# Spring2020V1_4.net
KiCad netlist of a schematic drawn in EAGLE
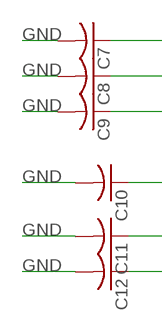
[diagram p0: schematic, sheet 1, part 1 of 2]
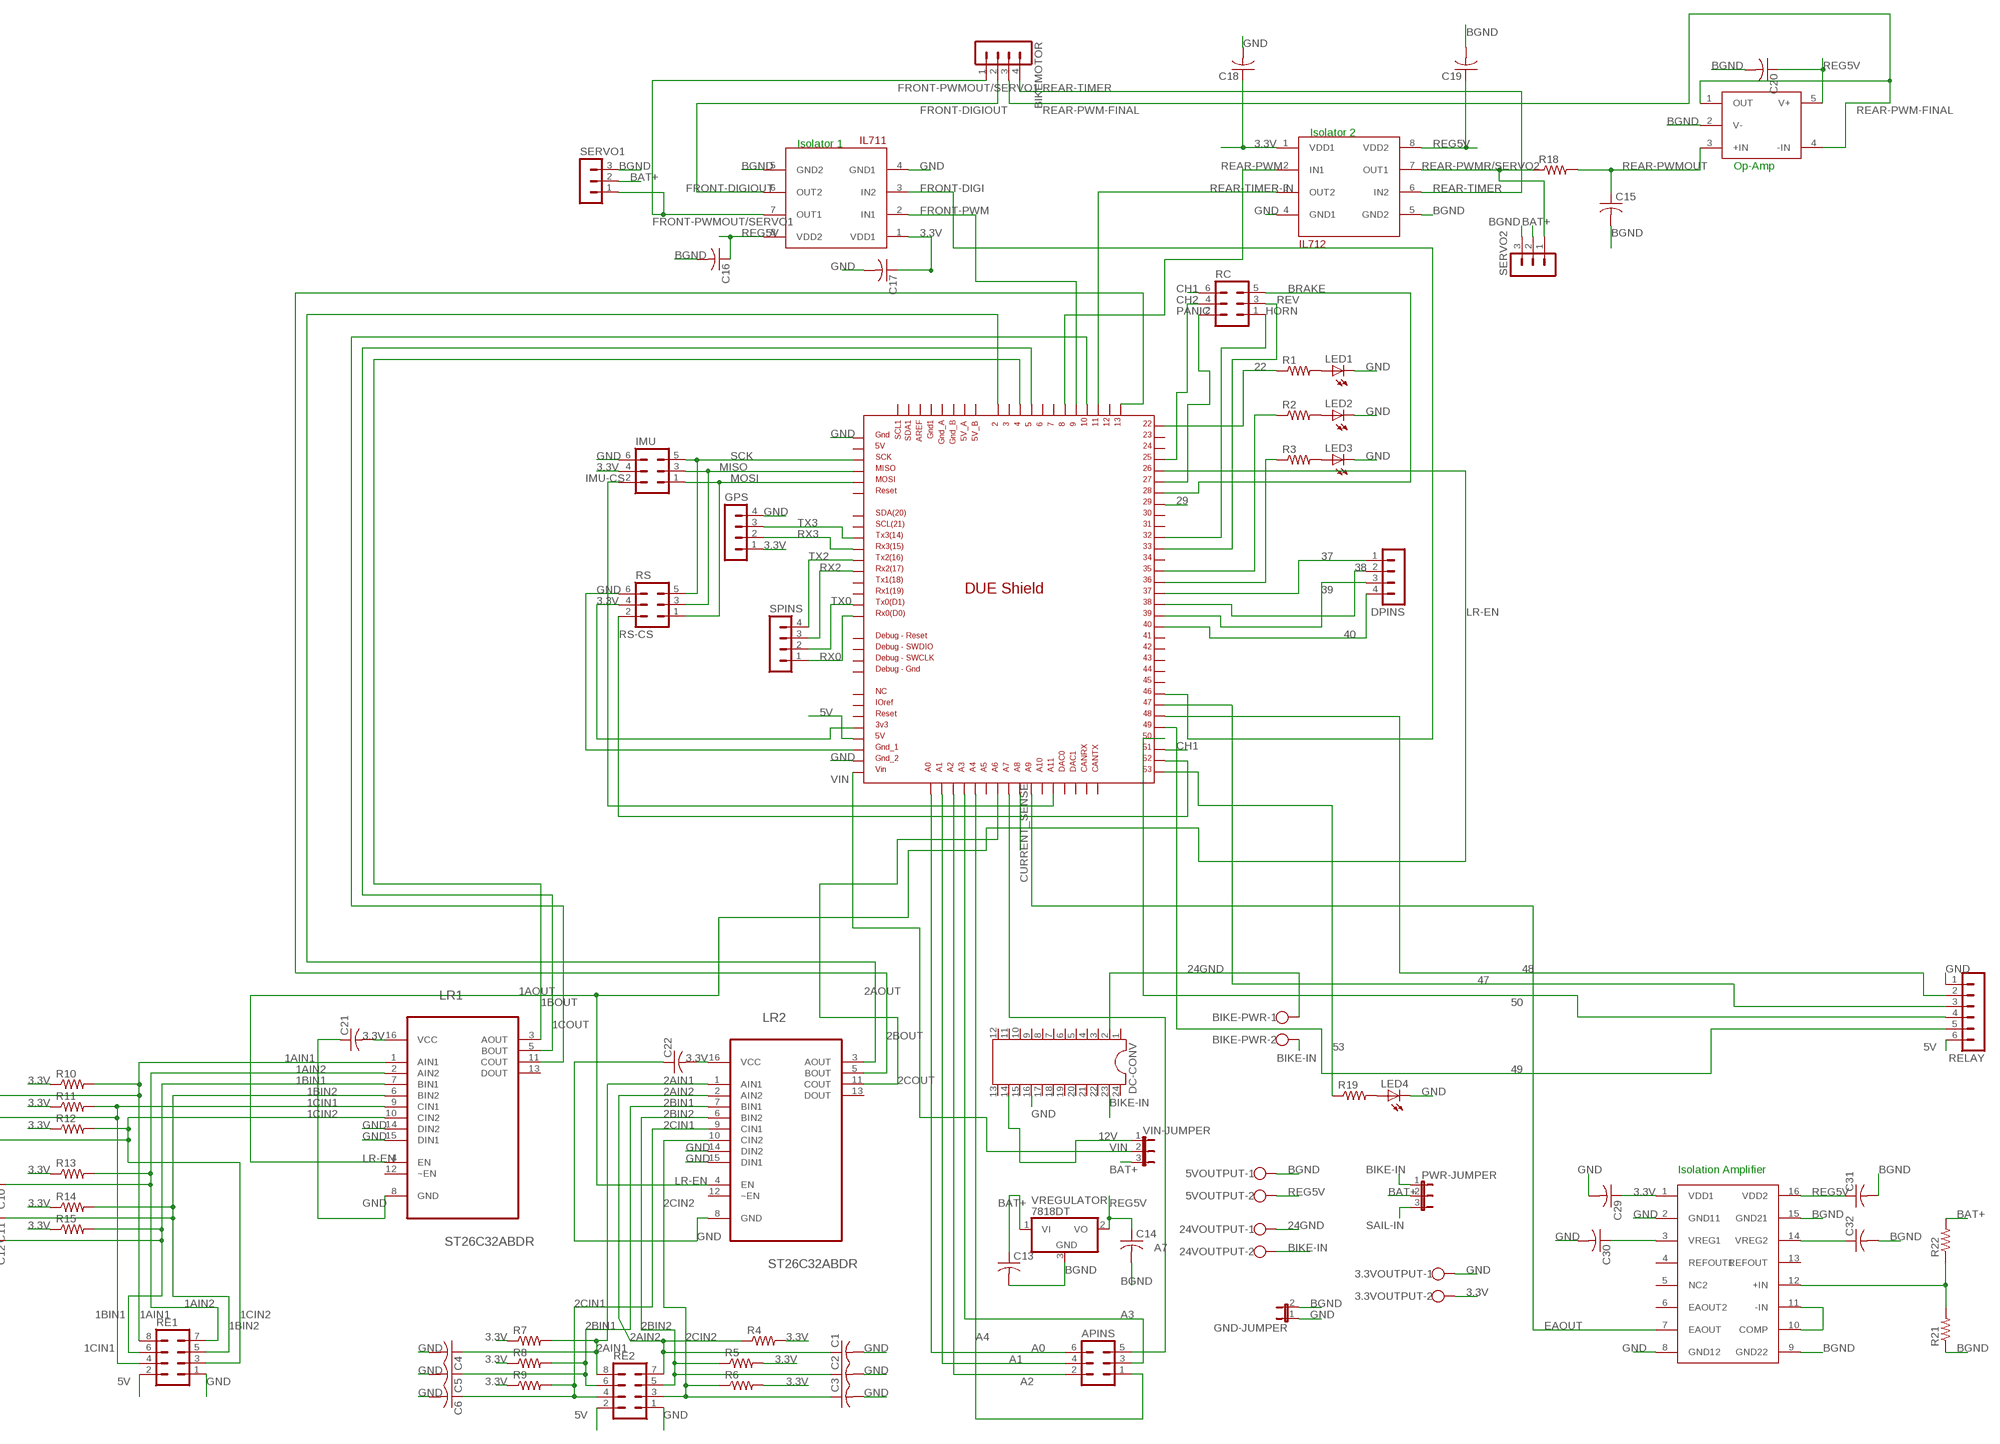
[diagram p1: schematic, sheet 1, part 2 of 2]

(export (version "E")
  (design (tool "Eeschema 10.0.6"))
  (components
    (comp (ref "3.3VOUTPUT")
      (value "W237-102")
      (footprint "eagle-import:W237-102")
      (fields (field (name "MPN") "237-102"))
      (libsource (lib "eagle-import") (part "W237-102"))
    )
    (comp (ref "5VOUTPUT")
      (value "W237-102")
      (footprint "eagle-import:W237-102")
      (fields (field (name "MPN") "237-102"))
      (libsource (lib "eagle-import") (part "W237-102"))
    )
    (comp (ref "24VOUTPUT")
      (value "W237-102")
      (footprint "eagle-import:W237-102")
      (fields (field (name "MPN") "237-102"))
      (libsource (lib "eagle-import") (part "W237-102"))
    )
    (comp (ref "APINS")
      (value "MA03-2")
      (footprint "eagle-import:MA03-2")
      (libsource (lib "eagle-import") (part "MA03-2"))
    )
    (comp (ref "BIKE-PWR")
      (value "W237-102")
      (footprint "eagle-import:W237-102")
      (fields (field (name "MPN") "237-102"))
      (libsource (lib "eagle-import") (part "W237-102"))
    )
    (comp (ref "BIKEMOTOR")
      (value "MA04-1")
      (footprint "eagle-import:MA04-1")
      (libsource (lib "eagle-import") (part "MA04-1"))
    )
    (comp (ref "C1")
      (value "C-US025-025X050")
      (footprint "eagle-import:C025-025X050")
      (libsource (lib "eagle-import") (part "C-US025-025X050"))
    )
    (comp (ref "C2")
      (value "C-US025-025X050")
      (footprint "eagle-import:C025-025X050")
      (libsource (lib "eagle-import") (part "C-US025-025X050"))
    )
    (comp (ref "C3")
      (value "C-US025-025X050")
      (footprint "eagle-import:C025-025X050")
      (libsource (lib "eagle-import") (part "C-US025-025X050"))
    )
    (comp (ref "C4")
      (value "C-US025-025X050")
      (footprint "eagle-import:C025-025X050")
      (libsource (lib "eagle-import") (part "C-US025-025X050"))
    )
    (comp (ref "C5")
      (value "C-US025-025X050")
      (footprint "eagle-import:C025-025X050")
      (libsource (lib "eagle-import") (part "C-US025-025X050"))
    )
    (comp (ref "C6")
      (value "C-US025-025X050")
      (footprint "eagle-import:C025-025X050")
      (libsource (lib "eagle-import") (part "C-US025-025X050"))
    )
    (comp (ref "C7")
      (value "C-US025-025X050")
      (footprint "eagle-import:C025-025X050")
      (libsource (lib "eagle-import") (part "C-US025-025X050"))
    )
    (comp (ref "C8")
      (value "C-US025-025X050")
      (footprint "eagle-import:C025-025X050")
      (libsource (lib "eagle-import") (part "C-US025-025X050"))
    )
    (comp (ref "C9")
      (value "C-US025-025X050")
      (footprint "eagle-import:C025-025X050")
      (libsource (lib "eagle-import") (part "C-US025-025X050"))
    )
    (comp (ref "C10")
      (value "C-US025-025X050")
      (footprint "eagle-import:C025-025X050")
      (libsource (lib "eagle-import") (part "C-US025-025X050"))
    )
    (comp (ref "C11")
      (value "C-US025-025X050")
      (footprint "eagle-import:C025-025X050")
      (libsource (lib "eagle-import") (part "C-US025-025X050"))
    )
    (comp (ref "C12")
      (value "C-US025-025X050")
      (footprint "eagle-import:C025-025X050")
      (libsource (lib "eagle-import") (part "C-US025-025X050"))
    )
    (comp (ref "C13")
      (value "C-US025-050X050")
      (footprint "eagle-import:C025-050X050")
      (libsource (lib "eagle-import") (part "C-US025-050X050"))
    )
    (comp (ref "C14")
      (value "C-US025-050X050")
      (footprint "eagle-import:C025-050X050")
      (libsource (lib "eagle-import") (part "C-US025-050X050"))
    )
    (comp (ref "C15")
      (value "C-US025-050X050")
      (footprint "eagle-import:C025-050X050")
      (libsource (lib "eagle-import") (part "C-US025-050X050"))
    )
    (comp (ref "C16")
      (value "C-US025-050X050")
      (footprint "eagle-import:C025-050X050")
      (libsource (lib "eagle-import") (part "C-US025-050X050"))
    )
    (comp (ref "C17")
      (value "C-US025-050X050")
      (footprint "eagle-import:C025-050X050")
      (libsource (lib "eagle-import") (part "C-US025-050X050"))
    )
    (comp (ref "C18")
      (value "C-US025-050X050")
      (footprint "eagle-import:C025-050X050")
      (libsource (lib "eagle-import") (part "C-US025-050X050"))
    )
    (comp (ref "C19")
      (value "C-US025-050X050")
      (footprint "eagle-import:C025-050X050")
      (libsource (lib "eagle-import") (part "C-US025-050X050"))
    )
    (comp (ref "C20")
      (value "C-US025-050X050")
      (footprint "eagle-import:C025-050X050")
      (libsource (lib "eagle-import") (part "C-US025-050X050"))
    )
    (comp (ref "C21")
      (value "C-US025-050X050")
      (footprint "eagle-import:C025-050X050")
      (libsource (lib "eagle-import") (part "C-US025-050X050"))
    )
    (comp (ref "C22")
      (value "C-US025-050X050")
      (footprint "eagle-import:C025-050X050")
      (libsource (lib "eagle-import") (part "C-US025-050X050"))
    )
    (comp (ref "C29")
      (value "C-US025-050X050")
      (footprint "eagle-import:C025-050X050")
      (libsource (lib "eagle-import") (part "C-US025-050X050"))
    )
    (comp (ref "C30")
      (value "C-US025-050X050")
      (footprint "eagle-import:C025-050X050")
      (libsource (lib "eagle-import") (part "C-US025-050X050"))
    )
    (comp (ref "C31")
      (value "C-US025-050X050")
      (footprint "eagle-import:C025-050X050")
      (libsource (lib "eagle-import") (part "C-US025-050X050"))
    )
    (comp (ref "C32")
      (value "C-US025-050X050")
      (footprint "eagle-import:C025-050X050")
      (libsource (lib "eagle-import") (part "C-US025-050X050"))
    )
    (comp (ref "DC-CONV")
      (value "CU.INC---VAWQ6-Q48-S12H-6")
      (footprint "eagle-import:DIL24-6")
      (libsource (lib "eagle-import") (part "CU.INC---VAWQ6-Q48-S12H-6"))
    )
    (comp (ref "DPINS")
      (value "MA04-1")
      (footprint "eagle-import:MA04-1")
      (libsource (lib "eagle-import") (part "MA04-1"))
    )
    (comp (ref "GND-JUMPER")
      (value "JP1E")
      (footprint "eagle-import:JP1")
      (libsource (lib "eagle-import") (part "JP1E"))
    )
    (comp (ref "GPS")
      (value "MA04-1")
      (footprint "eagle-import:MA04-1")
      (libsource (lib "eagle-import") (part "MA04-1"))
    )
    (comp (ref "IMU")
      (value "MA03-2")
      (footprint "eagle-import:MA03-2")
      (libsource (lib "eagle-import") (part "MA03-2"))
    )
    (comp (ref "LED1")
      (value "LED5MM")
      (footprint "eagle-import:LED5MM")
      (libsource (lib "eagle-import") (part "LED5MM"))
    )
    (comp (ref "LED2")
      (value "LED5MM")
      (footprint "eagle-import:LED5MM")
      (libsource (lib "eagle-import") (part "LED5MM"))
    )
    (comp (ref "LED3")
      (value "LED5MM")
      (footprint "eagle-import:LED5MM")
      (libsource (lib "eagle-import") (part "LED5MM"))
    )
    (comp (ref "LED4")
      (value "LED5MM")
      (footprint "eagle-import:LED5MM")
      (libsource (lib "eagle-import") (part "LED5MM"))
    )
    (comp (ref "LR1")
      (value "ST26C32ABDR")
      (footprint "eagle-import:SOIC127P600X175-16N")
      (libsource (lib "eagle-import") (part "ST26C32ABDR"))
    )
    (comp (ref "LR2")
      (value "ST26C32ABDR")
      (footprint "eagle-import:SOIC127P600X175-16N")
      (libsource (lib "eagle-import") (part "ST26C32ABDR"))
    )
    (comp (ref "OP-AMP")
      (value "OPAMP")
      (footprint "eagle-import:SOT95P280X145-5N")
      (libsource (lib "eagle-import") (part "OPAMP"))
    )
    (comp (ref "PWR-JUMPER")
      (value "JP2E")
      (footprint "eagle-import:JP2")
      (libsource (lib "eagle-import") (part "JP2E"))
    )
    (comp (ref "R1")
      (value "R-US_0309/10")
      (footprint "eagle-import:0309_10")
      (libsource (lib "eagle-import") (part "R-US_0309/10"))
    )
    (comp (ref "R2")
      (value "R-US_0309/10")
      (footprint "eagle-import:0309_10")
      (libsource (lib "eagle-import") (part "R-US_0309/10"))
    )
    (comp (ref "R3")
      (value "R-US_0309/10")
      (footprint "eagle-import:0309_10")
      (libsource (lib "eagle-import") (part "R-US_0309/10"))
    )
    (comp (ref "R4")
      (value "R-US_0613/15")
      (footprint "eagle-import:P0613_15")
      (libsource (lib "eagle-import") (part "resistor_R-US_0613/15"))
    )
    (comp (ref "R5")
      (value "R-US_0613/15")
      (footprint "eagle-import:P0613_15")
      (libsource (lib "eagle-import") (part "resistor_R-US_0613/15"))
    )
    (comp (ref "R6")
      (value "R-US_0613/15")
      (footprint "eagle-import:P0613_15")
      (libsource (lib "eagle-import") (part "resistor_R-US_0613/15"))
    )
    (comp (ref "R7")
      (value "R-US_0613/15")
      (footprint "eagle-import:P0613_15")
      (libsource (lib "eagle-import") (part "resistor_R-US_0613/15"))
    )
    (comp (ref "R8")
      (value "R-US_0613/15")
      (footprint "eagle-import:P0613_15")
      (libsource (lib "eagle-import") (part "resistor_R-US_0613/15"))
    )
    (comp (ref "R9")
      (value "R-US_0613/15")
      (footprint "eagle-import:P0613_15")
      (libsource (lib "eagle-import") (part "resistor_R-US_0613/15"))
    )
    (comp (ref "R10")
      (value "R-US_0613/15")
      (footprint "eagle-import:P0613_15")
      (libsource (lib "eagle-import") (part "resistor_R-US_0613/15"))
    )
    (comp (ref "R11")
      (value "R-US_0613/15")
      (footprint "eagle-import:P0613_15")
      (libsource (lib "eagle-import") (part "resistor_R-US_0613/15"))
    )
    (comp (ref "R12")
      (value "R-US_0613/15")
      (footprint "eagle-import:P0613_15")
      (libsource (lib "eagle-import") (part "resistor_R-US_0613/15"))
    )
    (comp (ref "R13")
      (value "R-US_0613/15")
      (footprint "eagle-import:P0613_15")
      (libsource (lib "eagle-import") (part "resistor_R-US_0613/15"))
    )
    (comp (ref "R14")
      (value "R-US_0613/15")
      (footprint "eagle-import:P0613_15")
      (libsource (lib "eagle-import") (part "resistor_R-US_0613/15"))
    )
    (comp (ref "R15")
      (value "R-US_0613/15")
      (footprint "eagle-import:P0613_15")
      (libsource (lib "eagle-import") (part "resistor_R-US_0613/15"))
    )
    (comp (ref "R18")
      (value "R-US_0414/15")
      (footprint "eagle-import:0414_15")
      (libsource (lib "eagle-import") (part "resistor_R-US_0414/15"))
    )
    (comp (ref "R19")
      (value "R-US_0309/10")
      (footprint "eagle-import:0309_10")
      (libsource (lib "eagle-import") (part "R-US_0309/10"))
    )
    (comp (ref "R21")
      (value "R-US_0414/15")
      (footprint "eagle-import:0414_15")
      (libsource (lib "eagle-import") (part "resistor_R-US_0414/15"))
    )
    (comp (ref "R22")
      (value "R-US_0414/15")
      (footprint "eagle-import:0414_15")
      (libsource (lib "eagle-import") (part "resistor_R-US_0414/15"))
    )
    (comp (ref "RC")
      (value "MA03-2")
      (footprint "eagle-import:MA03-2")
      (libsource (lib "eagle-import") (part "MA03-2"))
    )
    (comp (ref "RE1")
      (value "MA04-2")
      (footprint "eagle-import:MA04-2")
      (libsource (lib "eagle-import") (part "MA04-2"))
    )
    (comp (ref "RE2")
      (value "MA04-2")
      (footprint "eagle-import:MA04-2")
      (libsource (lib "eagle-import") (part "MA04-2"))
    )
    (comp (ref "RELAY")
      (value "MA06-1")
      (footprint "eagle-import:MA06-1")
      (libsource (lib "eagle-import") (part "MA06-1"))
    )
    (comp (ref "RS")
      (value "MA03-2")
      (footprint "eagle-import:MA03-2")
      (libsource (lib "eagle-import") (part "MA03-2"))
    )
    (comp (ref "SERVO1")
      (value "MA03-1")
      (footprint "eagle-import:MA03-1")
      (libsource (lib "eagle-import") (part "MA03-1"))
    )
    (comp (ref "SERVO2")
      (value "MA03-1")
      (footprint "eagle-import:MA03-1")
      (libsource (lib "eagle-import") (part "MA03-1"))
    )
    (comp (ref "SPINS")
      (value "MA04-1")
      (footprint "eagle-import:MA04-1")
      (libsource (lib "eagle-import") (part "MA04-1"))
    )
    (comp (ref "U$1")
      (value "DUE(NORMAL)")
      (footprint "eagle-import:DUE(NORMAL)")
      (libsource (lib "eagle-import") (part "DUE(NORMAL)"))
    )
    (comp (ref "U$2")
      (value "IL-711")
      (footprint "eagle-import:8PINSOIC")
      (libsource (lib "eagle-import") (part "IL-711"))
    )
    (comp (ref "U$5")
      (value "ISOLATED_ERROR_AMP_ADUM3190")
      (footprint "eagle-import:QSOP16")
      (libsource (lib "eagle-import") (part "ISOLATED_ERROR_AMP_ADUM3190"))
    )
    (comp (ref "U$7")
      (value "IL-712")
      (footprint "eagle-import:8PINSOIC")
      (libsource (lib "eagle-import") (part "IL-712"))
    )
    (comp (ref "VIN-JUMPER")
      (value "JP2E")
      (footprint "eagle-import:JP2")
      (libsource (lib "eagle-import") (part "JP2E"))
    )
    (comp (ref "VREGULATOR")
      (value "7818DT")
      (footprint "eagle-import:TO252")
      (libsource (lib "eagle-import") (part "78DT18"))
    )
  )
  (nets
    (net (code "1") (name "/1AIN1") (class "Default")
      (node (ref "C7") (pin "1") (pinfunction "1_1") (pintype "passive"))
      (node (ref "LR1") (pin "1") (pinfunction "AIN1_1") (pintype "input"))
      (node (ref "R10") (pin "2") (pinfunction "2_2") (pintype "passive"))
      (node (ref "RE1") (pin "8") (pinfunction "8_8") (pintype "passive"))
    )
    (net (code "2") (name "/1AIN2") (class "Default")
      (node (ref "C10") (pin "1") (pinfunction "1_1") (pintype "passive"))
      (node (ref "LR1") (pin "2") (pinfunction "AIN2_2") (pintype "input"))
      (node (ref "R13") (pin "2") (pinfunction "2_2") (pintype "passive"))
      (node (ref "RE1") (pin "7") (pinfunction "7_7") (pintype "passive"))
    )
    (net (code "3") (name "/1AOUT") (class "Default")
      (node (ref "LR1") (pin "3") (pinfunction "AOUT_3") (pintype "output"))
      (node (ref "U$1") (pin "4") (pinfunction "4_4") (pintype "bidirectional"))
    )
    (net (code "4") (name "/1BIN1") (class "Default")
      (node (ref "C12") (pin "1") (pinfunction "1_1") (pintype "passive"))
      (node (ref "LR1") (pin "7") (pinfunction "BIN1_7") (pintype "input"))
      (node (ref "R15") (pin "2") (pinfunction "2_2") (pintype "passive"))
      (node (ref "RE1") (pin "6") (pinfunction "6_6") (pintype "passive"))
    )
    (net (code "5") (name "/1BIN2") (class "Default")
      (node (ref "C11") (pin "1") (pinfunction "1_1") (pintype "passive"))
      (node (ref "LR1") (pin "6") (pinfunction "BIN2_6") (pintype "input"))
      (node (ref "R14") (pin "2") (pinfunction "2_2") (pintype "passive"))
      (node (ref "RE1") (pin "5") (pinfunction "5_5") (pintype "passive"))
    )
    (net (code "6") (name "/1BOUT") (class "Default")
      (node (ref "LR1") (pin "5") (pinfunction "BOUT_5") (pintype "output"))
      (node (ref "U$1") (pin "5") (pinfunction "5_5") (pintype "bidirectional"))
    )
    (net (code "7") (name "/1CIN1") (class "Default")
      (node (ref "C8") (pin "1") (pinfunction "1_1") (pintype "passive"))
      (node (ref "LR1") (pin "9") (pinfunction "CIN1_9") (pintype "input"))
      (node (ref "R11") (pin "2") (pinfunction "2_2") (pintype "passive"))
      (node (ref "RE1") (pin "4") (pinfunction "4_4") (pintype "passive"))
    )
    (net (code "8") (name "/1CIN2") (class "Default")
      (node (ref "C9") (pin "1") (pinfunction "1_1") (pintype "passive"))
      (node (ref "LR1") (pin "10") (pinfunction "CIN2_10") (pintype "input"))
      (node (ref "R12") (pin "2") (pinfunction "2_2") (pintype "passive"))
      (node (ref "RE1") (pin "3") (pinfunction "3_3") (pintype "passive"))
    )
    (net (code "9") (name "/1COUT") (class "Default")
      (node (ref "LR1") (pin "11") (pinfunction "COUT_11") (pintype "output"))
      (node (ref "U$1") (pin "10") (pinfunction "10_10") (pintype "bidirectional"))
    )
    (net (code "10") (name "/2AIN1") (class "Default")
      (node (ref "C4") (pin "1") (pinfunction "1_1") (pintype "passive"))
      (node (ref "LR2") (pin "1") (pinfunction "AIN1_1") (pintype "input"))
      (node (ref "R7") (pin "2") (pinfunction "2_2") (pintype "passive"))
      (node (ref "RE2") (pin "8") (pinfunction "8_8") (pintype "passive"))
    )
    (net (code "11") (name "/2AIN2") (class "Default")
      (node (ref "C1") (pin "1") (pinfunction "1_1") (pintype "passive"))
      (node (ref "LR2") (pin "2") (pinfunction "AIN2_2") (pintype "input"))
      (node (ref "R4") (pin "1") (pinfunction "1_1") (pintype "passive"))
      (node (ref "RE2") (pin "7") (pinfunction "7_7") (pintype "passive"))
    )
    (net (code "12") (name "/2AOUT") (class "Default")
      (node (ref "LR2") (pin "3") (pinfunction "AOUT_3") (pintype "output"))
      (node (ref "U$1") (pin "2") (pinfunction "2_2") (pintype "bidirectional"))
    )
    (net (code "13") (name "/2BIN1") (class "Default")
      (node (ref "C5") (pin "1") (pinfunction "1_1") (pintype "passive"))
      (node (ref "LR2") (pin "7") (pinfunction "BIN1_7") (pintype "input"))
      (node (ref "R8") (pin "2") (pinfunction "2_2") (pintype "passive"))
      (node (ref "RE2") (pin "6") (pinfunction "6_6") (pintype "passive"))
    )
    (net (code "14") (name "/2BIN2") (class "Default")
      (node (ref "C2") (pin "1") (pinfunction "1_1") (pintype "passive"))
      (node (ref "LR2") (pin "6") (pinfunction "BIN2_6") (pintype "input"))
      (node (ref "R5") (pin "1") (pinfunction "1_1") (pintype "passive"))
      (node (ref "RE2") (pin "5") (pinfunction "5_5") (pintype "passive"))
    )
    (net (code "15") (name "/2BOUT") (class "Default")
      (node (ref "LR2") (pin "5") (pinfunction "BOUT_5") (pintype "output"))
      (node (ref "U$1") (pin "13") (pinfunction "13_13") (pintype "bidirectional"))
    )
    (net (code "16") (name "/2CIN1") (class "Default")
      (node (ref "C6") (pin "1") (pinfunction "1_1") (pintype "passive"))
      (node (ref "LR2") (pin "9") (pinfunction "CIN1_9") (pintype "input"))
      (node (ref "R9") (pin "2") (pinfunction "2_2") (pintype "passive"))
      (node (ref "RE2") (pin "4") (pinfunction "4_4") (pintype "passive"))
    )
    (net (code "17") (name "/2CIN2") (class "Default")
      (node (ref "C3") (pin "1") (pinfunction "1_1") (pintype "passive"))
      (node (ref "LR2") (pin "10") (pinfunction "CIN2_10") (pintype "input"))
      (node (ref "R6") (pin "1") (pinfunction "1_1") (pintype "passive"))
      (node (ref "RE2") (pin "3") (pinfunction "3_3") (pintype "passive"))
    )
    (net (code "18") (name "/2COUT") (class "Default")
      (node (ref "LR2") (pin "11") (pinfunction "COUT_11") (pintype "output"))
      (node (ref "U$1") (pin "A6") (pinfunction "A6_A6") (pintype "bidirectional"))
    )
    (net (code "19") (name "/3.3V") (class "Default")
      (node (ref "3.3VOUTPUT") (pin "2") (pinfunction "KL_2") (pintype "passive"))
      (node (ref "C17") (pin "1") (pinfunction "1_1") (pintype "passive"))
      (node (ref "C18") (pin "1") (pinfunction "1_1") (pintype "passive"))
      (node (ref "C21") (pin "2") (pinfunction "2_2") (pintype "passive"))
      (node (ref "C22") (pin "2") (pinfunction "2_2") (pintype "passive"))
      (node (ref "C29") (pin "1") (pinfunction "1_1") (pintype "passive"))
      (node (ref "GPS") (pin "1") (pinfunction "1_1") (pintype "passive"))
      (node (ref "IMU") (pin "4") (pinfunction "4_4") (pintype "passive"))
      (node (ref "LR1") (pin "16") (pinfunction "VCC_16") (pintype "power_in"))
      (node (ref "LR2") (pin "16") (pinfunction "VCC_16") (pintype "power_in"))
      (node (ref "R10") (pin "1") (pinfunction "1_1") (pintype "passive"))
      (node (ref "R11") (pin "1") (pinfunction "1_1") (pintype "passive"))
      (node (ref "R12") (pin "1") (pinfunction "1_1") (pintype "passive"))
      (node (ref "R13") (pin "1") (pinfunction "1_1") (pintype "passive"))
      (node (ref "R14") (pin "1") (pinfunction "1_1") (pintype "passive"))
      (node (ref "R15") (pin "1") (pinfunction "1_1") (pintype "passive"))
      (node (ref "R4") (pin "2") (pinfunction "2_2") (pintype "passive"))
      (node (ref "R5") (pin "2") (pinfunction "2_2") (pintype "passive"))
      (node (ref "R6") (pin "2") (pinfunction "2_2") (pintype "passive"))
      (node (ref "R7") (pin "1") (pinfunction "1_1") (pintype "passive"))
      (node (ref "R8") (pin "1") (pinfunction "1_1") (pintype "passive"))
      (node (ref "R9") (pin "1") (pinfunction "1_1") (pintype "passive"))
      (node (ref "RS") (pin "4") (pinfunction "4_4") (pintype "passive"))
      (node (ref "U$1") (pin "3V3") (pinfunction "3V3_3V3") (pintype "bidirectional"))
      (node (ref "U$2") (pin "1") (pinfunction "VDD1_1") (pintype "power_in"))
      (node (ref "U$5") (pin "1") (pinfunction "VDD1_1") (pintype "bidirectional"))
      (node (ref "U$7") (pin "1") (pinfunction "VDD1_1") (pintype "power_in"))
    )
    (net (code "20") (name "/5V") (class "Default")
      (node (ref "RE1") (pin "2") (pinfunction "2_2") (pintype "passive"))
      (node (ref "RE2") (pin "2") (pinfunction "2_2") (pintype "passive"))
      (node (ref "RELAY") (pin "6") (pinfunction "6_6") (pintype "passive"))
      (node (ref "U$1") (pin "5V") (pinfunction "5V_5V") (pintype "bidirectional"))
    )
    (net (code "21") (name "/12V") (class "Default")
      (node (ref "DC-CONV") (pin "14") (pinfunction "14_14") (pintype "passive"))
      (node (ref "VIN-JUMPER") (pin "1") (pinfunction "1_1") (pintype "passive"))
    )
    (net (code "22") (name "/22") (class "Default")
      (node (ref "R1") (pin "1") (pinfunction "1_1") (pintype "passive"))
      (node (ref "U$1") (pin "22") (pinfunction "22_22") (pintype "bidirectional"))
    )
    (net (code "23") (name "/24GND") (class "Default")
      (node (ref "24VOUTPUT") (pin "1") (pinfunction "KL_1") (pintype "passive"))
      (node (ref "BIKE-PWR") (pin "1") (pinfunction "KL_1") (pintype "passive"))
      (node (ref "DC-CONV") (pin "2") (pinfunction "2_2") (pintype "passive"))
    )
    (net (code "24") (name "/29") (class "Default")
      (node (ref "U$1") (pin "29") (pinfunction "29_29") (pintype "bidirectional"))
    )
    (net (code "25") (name "/37") (class "Default")
      (node (ref "DPINS") (pin "1") (pinfunction "1_1") (pintype "passive"))
      (node (ref "U$1") (pin "37") (pinfunction "37_37") (pintype "bidirectional"))
    )
    (net (code "26") (name "/38") (class "Default")
      (node (ref "DPINS") (pin "2") (pinfunction "2_2") (pintype "passive"))
      (node (ref "U$1") (pin "38") (pinfunction "38_38") (pintype "bidirectional"))
    )
    (net (code "27") (name "/39") (class "Default")
      (node (ref "DPINS") (pin "3") (pinfunction "3_3") (pintype "passive"))
      (node (ref "U$1") (pin "39") (pinfunction "39_39") (pintype "bidirectional"))
    )
    (net (code "28") (name "/40") (class "Default")
      (node (ref "DPINS") (pin "4") (pinfunction "4_4") (pintype "passive"))
      (node (ref "U$1") (pin "40") (pinfunction "40_40") (pintype "bidirectional"))
    )
    (net (code "29") (name "/47") (class "Default")
      (node (ref "RELAY") (pin "3") (pinfunction "3_3") (pintype "passive"))
      (node (ref "U$1") (pin "47") (pinfunction "47_47") (pintype "bidirectional"))
    )
    (net (code "30") (name "/48") (class "Default")
      (node (ref "RELAY") (pin "2") (pinfunction "2_2") (pintype "passive"))
      (node (ref "U$1") (pin "48") (pinfunction "48_48") (pintype "bidirectional"))
    )
    (net (code "31") (name "/49") (class "Default")
      (node (ref "RELAY") (pin "5") (pinfunction "5_5") (pintype "passive"))
      (node (ref "U$1") (pin "49") (pinfunction "49_49") (pintype "bidirectional"))
    )
    (net (code "32") (name "/50") (class "Default")
      (node (ref "RELAY") (pin "4") (pinfunction "4_4") (pintype "passive"))
      (node (ref "U$1") (pin "50") (pinfunction "50_50") (pintype "bidirectional"))
    )
    (net (code "33") (name "/53") (class "Default")
      (node (ref "R19") (pin "1") (pinfunction "1_1") (pintype "passive"))
      (node (ref "U$1") (pin "53") (pinfunction "53_53") (pintype "bidirectional"))
    )
    (net (code "34") (name "/A0") (class "Default")
      (node (ref "APINS") (pin "6") (pinfunction "6_6") (pintype "passive"))
      (node (ref "U$1") (pin "A0") (pinfunction "A0_A0") (pintype "bidirectional"))
    )
    (net (code "35") (name "/A1") (class "Default")
      (node (ref "APINS") (pin "4") (pinfunction "4_4") (pintype "passive"))
      (node (ref "U$1") (pin "A1") (pinfunction "A1_A1") (pintype "bidirectional"))
    )
    (net (code "36") (name "/A2") (class "Default")
      (node (ref "APINS") (pin "2") (pinfunction "2_2") (pintype "passive"))
      (node (ref "U$1") (pin "A2") (pinfunction "A2_A2") (pintype "bidirectional"))
    )
    (net (code "37") (name "/A3") (class "Default")
      (node (ref "APINS") (pin "3") (pinfunction "3_3") (pintype "passive"))
      (node (ref "U$1") (pin "A3") (pinfunction "A3_A3") (pintype "bidirectional"))
    )
    (net (code "38") (name "/A4") (class "Default")
      (node (ref "APINS") (pin "1") (pinfunction "1_1") (pintype "passive"))
      (node (ref "U$1") (pin "A4") (pinfunction "A4_A4") (pintype "bidirectional"))
    )
    (net (code "39") (name "/A7") (class "Default")
      (node (ref "APINS") (pin "5") (pinfunction "5_5") (pintype "passive"))
      (node (ref "U$1") (pin "A7") (pinfunction "A7_A7") (pintype "bidirectional"))
    )
    (net (code "40") (name "/BAT+") (class "Default")
      (node (ref "C13") (pin "1") (pinfunction "1_1") (pintype "passive"))
      (node (ref "PWR-JUMPER") (pin "2") (pinfunction "2_2") (pintype "passive"))
      (node (ref "R22") (pin "2") (pinfunction "2_2") (pintype "passive"))
      (node (ref "SERVO1") (pin "2") (pinfunction "2_2") (pintype "passive"))
      (node (ref "SERVO2") (pin "2") (pinfunction "2_2") (pintype "passive"))
      (node (ref "VIN-JUMPER") (pin "3") (pinfunction "3_3") (pintype "passive"))
      (node (ref "VREGULATOR") (pin "1") (pinfunction "VI_1") (pintype "input"))
    )
    (net (code "41") (name "/BGND") (class "Default")
      (node (ref "5VOUTPUT") (pin "1") (pinfunction "KL_1") (pintype "passive"))
      (node (ref "C13") (pin "2") (pinfunction "2_2") (pintype "passive"))
      (node (ref "C14") (pin "2") (pinfunction "2_2") (pintype "passive"))
      (node (ref "C15") (pin "2") (pinfunction "2_2") (pintype "passive"))
      (node (ref "C16") (pin "2") (pinfunction "2_2") (pintype "passive"))
      (node (ref "C19") (pin "2") (pinfunction "2_2") (pintype "passive"))
      (node (ref "C20") (pin "2") (pinfunction "2_2") (pintype "passive"))
      (node (ref "C31") (pin "2") (pinfunction "2_2") (pintype "passive"))
      (node (ref "C32") (pin "2") (pinfunction "2_2") (pintype "passive"))
      (node (ref "GND-JUMPER") (pin "2") (pinfunction "2_2") (pintype "passive"))
      (node (ref "OP-AMP") (pin "2") (pinfunction "V-_2") (pintype "output"))
      (node (ref "R21") (pin "1") (pinfunction "1_1") (pintype "passive"))
      (node (ref "SERVO1") (pin "3") (pinfunction "3_3") (pintype "passive"))
      (node (ref "SERVO2") (pin "3") (pinfunction "3_3") (pintype "passive"))
      (node (ref "U$2") (pin "5") (pinfunction "GND2_5") (pintype "power_in"))
      (node (ref "U$5") (pin "15") (pinfunction "GND21_15") (pintype "bidirectional"))
      (node (ref "U$5") (pin "9") (pinfunction "GND22_9") (pintype "bidirectional"))
      (node (ref "U$7") (pin "5") (pinfunction "GND2_5") (pintype "power_in"))
      (node (ref "VREGULATOR") (pin "3") (pinfunction "GND_3") (pintype "passive"))
    )
    (net (code "42") (name "/BIKE-IN") (class "Default")
      (node (ref "24VOUTPUT") (pin "2") (pinfunction "KL_2") (pintype "passive"))
      (node (ref "BIKE-PWR") (pin "2") (pinfunction "KL_2") (pintype "passive"))
      (node (ref "DC-CONV") (pin "23") (pinfunction "23_23") (pintype "passive"))
      (node (ref "PWR-JUMPER") (pin "1") (pinfunction "1_1") (pintype "passive"))
    )
    (net (code "43") (name "/BRAKE") (class "Default")
      (node (ref "RC") (pin "5") (pinfunction "5_5") (pintype "passive"))
      (node (ref "U$1") (pin "28") (pinfunction "28_28") (pintype "bidirectional"))
    )
    (net (code "44") (name "/CH1") (class "Default")
      (node (ref "RC") (pin "6") (pinfunction "6_6") (pintype "passive"))
      (node (ref "U$1") (pin "51") (pinfunction "51_51") (pintype "bidirectional"))
    )
    (net (code "45") (name "/CH2") (class "Default")
      (node (ref "RC") (pin "4") (pinfunction "4_4") (pintype "passive"))
      (node (ref "U$1") (pin "25") (pinfunction "25_25") (pintype "bidirectional"))
    )
    (net (code "46") (name "/CURRENT_SENSE") (class "Default")
      (node (ref "U$1") (pin "A8") (pinfunction "A8_A8") (pintype "bidirectional"))
    )
    (net (code "47") (name "/EAOUT") (class "Default")
      (node (ref "U$1") (pin "A9") (pinfunction "A9_A9") (pintype "bidirectional"))
      (node (ref "U$5") (pin "7") (pinfunction "EAOUT_7") (pintype "bidirectional"))
    )
    (net (code "48") (name "/FRONT-DIGI") (class "Default")
      (node (ref "U$1") (pin "46") (pinfunction "46_46") (pintype "bidirectional"))
      (node (ref "U$2") (pin "3") (pinfunction "IN2_3") (pintype "input"))
    )
    (net (code "49") (name "/FRONT-DIGIOUT") (class "Default")
      (node (ref "BIKEMOTOR") (pin "2") (pinfunction "2_2") (pintype "passive"))
      (node (ref "U$2") (pin "6") (pinfunction "OUT2_6") (pintype "output"))
    )
    (net (code "50") (name "/FRONT-PWM") (class "Default")
      (node (ref "U$1") (pin "9") (pinfunction "9_9") (pintype "bidirectional"))
      (node (ref "U$2") (pin "2") (pinfunction "IN1_2") (pintype "input"))
    )
    (net (code "51") (name "/FRONT-PWMOUT{slash}SERVO1") (class "Default")
      (node (ref "BIKEMOTOR") (pin "1") (pinfunction "1_1") (pintype "passive"))
      (node (ref "SERVO1") (pin "1") (pinfunction "1_1") (pintype "passive"))
      (node (ref "U$2") (pin "7") (pinfunction "OUT1_7") (pintype "output"))
    )
    (net (code "52") (name "/GND") (class "Default")
      (node (ref "3.3VOUTPUT") (pin "1") (pinfunction "KL_1") (pintype "passive"))
      (node (ref "C1") (pin "2") (pinfunction "2_2") (pintype "passive"))
      (node (ref "C10") (pin "2") (pinfunction "2_2") (pintype "passive"))
      (node (ref "C11") (pin "2") (pinfunction "2_2") (pintype "passive"))
      (node (ref "C12") (pin "2") (pinfunction "2_2") (pintype "passive"))
      (node (ref "C17") (pin "2") (pinfunction "2_2") (pintype "passive"))
      (node (ref "C18") (pin "2") (pinfunction "2_2") (pintype "passive"))
      (node (ref "C2") (pin "2") (pinfunction "2_2") (pintype "passive"))
      (node (ref "C21") (pin "1") (pinfunction "1_1") (pintype "passive"))
      (node (ref "C22") (pin "1") (pinfunction "1_1") (pintype "passive"))
      (node (ref "C29") (pin "2") (pinfunction "2_2") (pintype "passive"))
      (node (ref "C3") (pin "2") (pinfunction "2_2") (pintype "passive"))
      (node (ref "C30") (pin "2") (pinfunction "2_2") (pintype "passive"))
      (node (ref "C4") (pin "2") (pinfunction "2_2") (pintype "passive"))
      (node (ref "C5") (pin "2") (pinfunction "2_2") (pintype "passive"))
      (node (ref "C6") (pin "2") (pinfunction "2_2") (pintype "passive"))
      (node (ref "C7") (pin "2") (pinfunction "2_2") (pintype "passive"))
      (node (ref "C8") (pin "2") (pinfunction "2_2") (pintype "passive"))
      (node (ref "C9") (pin "2") (pinfunction "2_2") (pintype "passive"))
      (node (ref "DC-CONV") (pin "16") (pinfunction "16_16") (pintype "passive"))
      (node (ref "GND-JUMPER") (pin "1") (pinfunction "1_1") (pintype "passive"))
      (node (ref "GPS") (pin "4") (pinfunction "4_4") (pintype "passive"))
      (node (ref "IMU") (pin "6") (pinfunction "6_6") (pintype "passive"))
      (node (ref "LED1") (pin "K") (pinfunction "C_K") (pintype "passive"))
      (node (ref "LED2") (pin "K") (pinfunction "C_K") (pintype "passive"))
      (node (ref "LED3") (pin "K") (pinfunction "C_K") (pintype "passive"))
      (node (ref "LED4") (pin "K") (pinfunction "C_K") (pintype "passive"))
      (node (ref "LR1") (pin "14") (pinfunction "DIN2_14") (pintype "input"))
      (node (ref "LR1") (pin "15") (pinfunction "DIN1_15") (pintype "input"))
      (node (ref "LR1") (pin "8") (pinfunction "GND_8") (pintype "passive"))
      (node (ref "LR2") (pin "14") (pinfunction "DIN2_14") (pintype "input"))
      (node (ref "LR2") (pin "15") (pinfunction "DIN1_15") (pintype "input"))
      (node (ref "LR2") (pin "8") (pinfunction "GND_8") (pintype "passive"))
      (node (ref "RE1") (pin "1") (pinfunction "1_1") (pintype "passive"))
      (node (ref "RE2") (pin "1") (pinfunction "1_1") (pintype "passive"))
      (node (ref "RELAY") (pin "1") (pinfunction "1_1") (pintype "passive"))
      (node (ref "RS") (pin "6") (pinfunction "6_6") (pintype "passive"))
      (node (ref "U$1") (pin "5V_ICSP") (pinfunction "5V_ICSP_5V_ICSP") (pintype "bidirectional"))
      (node (ref "U$1") (pin "GND_1") (pinfunction "GND_1_GND_1") (pintype "bidirectional"))
      (node (ref "U$1") (pin "GND_2") (pinfunction "GND_2_GND_2") (pintype "bidirectional"))
      (node (ref "U$2") (pin "4") (pinfunction "GND1_4") (pintype "power_in"))
      (node (ref "U$5") (pin "2") (pinfunction "GND11_2") (pintype "bidirectional"))
      (node (ref "U$5") (pin "8") (pinfunction "GND12_8") (pintype "bidirectional"))
      (node (ref "U$7") (pin "4") (pinfunction "GND1_4") (pintype "power_in"))
    )
    (net (code "53") (name "/HORN") (class "Default")
      (node (ref "RC") (pin "1") (pinfunction "1_1") (pintype "passive"))
      (node (ref "U$1") (pin "32") (pinfunction "32_32") (pintype "bidirectional"))
    )
    (net (code "54") (name "/IMU-CS") (class "Default")
      (node (ref "IMU") (pin "2") (pinfunction "2_2") (pintype "passive"))
      (node (ref "U$1") (pin "A11") (pinfunction "A11_A11") (pintype "bidirectional"))
    )
    (net (code "55") (name "/LR-EN") (class "Default")
      (node (ref "LR1") (pin "4") (pinfunction "EN_4") (pintype "input"))
      (node (ref "LR2") (pin "4") (pinfunction "EN_4") (pintype "input"))
      (node (ref "U$1") (pin "26") (pinfunction "26_26") (pintype "bidirectional"))
    )
    (net (code "56") (name "/MISO") (class "Default")
      (node (ref "IMU") (pin "3") (pinfunction "3_3") (pintype "passive"))
      (node (ref "RS") (pin "3") (pinfunction "3_3") (pintype "passive"))
      (node (ref "U$1") (pin "MISO_ICSP") (pinfunction "MISO_ICSP_MISO_ICSP") (pintype "bidirectional"))
    )
    (net (code "57") (name "/MOSI") (class "Default")
      (node (ref "IMU") (pin "1") (pinfunction "1_1") (pintype "passive"))
      (node (ref "RS") (pin "1") (pinfunction "1_1") (pintype "passive"))
      (node (ref "U$1") (pin "MOSI_ICSP") (pinfunction "MOSI_ICSP_MOSI_ICSP") (pintype "bidirectional"))
    )
    (net (code "58") (name "/PANIC") (class "Default")
      (node (ref "RC") (pin "2") (pinfunction "2_2") (pintype "passive"))
      (node (ref "U$1") (pin "27") (pinfunction "27_27") (pintype "bidirectional"))
    )
    (net (code "59") (name "/REAR-PWM") (class "Default")
      (node (ref "U$1") (pin "8") (pinfunction "8_8") (pintype "bidirectional"))
      (node (ref "U$7") (pin "2") (pinfunction "IN1_2") (pintype "input"))
    )
    (net (code "60") (name "/REAR-PWM-FINAL") (class "Default")
      (node (ref "BIKEMOTOR") (pin "3") (pinfunction "3_3") (pintype "passive"))
      (node (ref "OP-AMP") (pin "1") (pinfunction "OUT_1") (pintype "output"))
      (node (ref "OP-AMP") (pin "4") (pinfunction "-IN_4") (pintype "input"))
    )
    (net (code "61") (name "/REAR-PWMOUT") (class "Default")
      (node (ref "C15") (pin "1") (pinfunction "1_1") (pintype "passive"))
      (node (ref "OP-AMP") (pin "3") (pinfunction "+IN_3") (pintype "input"))
      (node (ref "R18") (pin "2") (pinfunction "2_2") (pintype "passive"))
    )
    (net (code "62") (name "/REAR-PWMR{slash}SERVO2") (class "Default")
      (node (ref "R18") (pin "1") (pinfunction "1_1") (pintype "passive"))
      (node (ref "SERVO2") (pin "1") (pinfunction "1_1") (pintype "passive"))
      (node (ref "U$7") (pin "7") (pinfunction "OUT1_7") (pintype "output"))
    )
    (net (code "63") (name "/REAR-TIMER") (class "Default")
      (node (ref "BIKEMOTOR") (pin "4") (pinfunction "4_4") (pintype "passive"))
      (node (ref "U$7") (pin "6") (pinfunction "IN2_6") (pintype "input"))
    )
    (net (code "64") (name "/REAR-TIMER-IN") (class "Default")
      (node (ref "U$1") (pin "11") (pinfunction "11_11") (pintype "bidirectional"))
      (node (ref "U$7") (pin "3") (pinfunction "OUT2_3") (pintype "output"))
    )
    (net (code "65") (name "/REG5V") (class "Default")
      (node (ref "5VOUTPUT") (pin "2") (pinfunction "KL_2") (pintype "passive"))
      (node (ref "C14") (pin "1") (pinfunction "1_1") (pintype "passive"))
      (node (ref "C16") (pin "1") (pinfunction "1_1") (pintype "passive"))
      (node (ref "C19") (pin "1") (pinfunction "1_1") (pintype "passive"))
      (node (ref "C20") (pin "1") (pinfunction "1_1") (pintype "passive"))
      (node (ref "C31") (pin "1") (pinfunction "1_1") (pintype "passive"))
      (node (ref "OP-AMP") (pin "5") (pinfunction "V+_5") (pintype "power_in"))
      (node (ref "U$2") (pin "8") (pinfunction "VDD2_8") (pintype "power_in"))
      (node (ref "U$5") (pin "16") (pinfunction "VDD2_16") (pintype "bidirectional"))
      (node (ref "U$7") (pin "8") (pinfunction "VDD2_8") (pintype "power_in"))
      (node (ref "VREGULATOR") (pin "2") (pinfunction "VO_2") (pintype "passive"))
    )
    (net (code "66") (name "/REV") (class "Default")
      (node (ref "RC") (pin "3") (pinfunction "3_3") (pintype "passive"))
      (node (ref "U$1") (pin "33") (pinfunction "33_33") (pintype "bidirectional"))
    )
    (net (code "67") (name "/RS-CS") (class "Default")
      (node (ref "RS") (pin "2") (pinfunction "2_2") (pintype "passive"))
      (node (ref "U$1") (pin "52") (pinfunction "52_52") (pintype "bidirectional"))
    )
    (net (code "68") (name "/RX0") (class "Default")
      (node (ref "SPINS") (pin "1") (pinfunction "1_1") (pintype "passive"))
      (node (ref "U$1") (pin "RX0") (pinfunction "RX0_RX0") (pintype "bidirectional"))
    )
    (net (code "69") (name "/RX2") (class "Default")
      (node (ref "SPINS") (pin "3") (pinfunction "3_3") (pintype "passive"))
      (node (ref "U$1") (pin "RX2") (pinfunction "RX2_RX2") (pintype "bidirectional"))
    )
    (net (code "70") (name "/RX3") (class "Default")
      (node (ref "GPS") (pin "2") (pinfunction "2_2") (pintype "passive"))
      (node (ref "U$1") (pin "RX3") (pinfunction "RX3_RX3") (pintype "bidirectional"))
    )
    (net (code "71") (name "/SAIL-IN") (class "Default")
      (node (ref "PWR-JUMPER") (pin "3") (pinfunction "3_3") (pintype "passive"))
    )
    (net (code "72") (name "/SCK") (class "Default")
      (node (ref "IMU") (pin "5") (pinfunction "5_5") (pintype "passive"))
      (node (ref "RS") (pin "5") (pinfunction "5_5") (pintype "passive"))
      (node (ref "U$1") (pin "SCK_ICSP") (pinfunction "SCK_ICSP_SCK_ICSP") (pintype "bidirectional"))
    )
    (net (code "73") (name "/TX0") (class "Default")
      (node (ref "SPINS") (pin "2") (pinfunction "2_2") (pintype "passive"))
      (node (ref "U$1") (pin "TX0") (pinfunction "TX0_TX0") (pintype "bidirectional"))
    )
    (net (code "74") (name "/TX2") (class "Default")
      (node (ref "SPINS") (pin "4") (pinfunction "4_4") (pintype "passive"))
      (node (ref "U$1") (pin "TX2") (pinfunction "TX2_TX2") (pintype "bidirectional"))
    )
    (net (code "75") (name "/TX3") (class "Default")
      (node (ref "GPS") (pin "3") (pinfunction "3_3") (pintype "passive"))
      (node (ref "U$1") (pin "TX3") (pinfunction "TX3_TX3") (pintype "bidirectional"))
    )
    (net (code "76") (name "/VIN") (class "Default")
      (node (ref "U$1") (pin "VIN") (pinfunction "VIN_VIN") (pintype "bidirectional"))
      (node (ref "VIN-JUMPER") (pin "2") (pinfunction "2_2") (pintype "passive"))
    )
    (net (code "77") (name "Net-(LED1-PadA)") (class "Default")
      (node (ref "LED1") (pin "A") (pinfunction "A_A") (pintype "passive"))
      (node (ref "R1") (pin "2") (pinfunction "2_2") (pintype "passive"))
    )
    (net (code "78") (name "Net-(LED2-PadA)") (class "Default")
      (node (ref "LED2") (pin "A") (pinfunction "A_A") (pintype "passive"))
      (node (ref "R2") (pin "2") (pinfunction "2_2") (pintype "passive"))
    )
    (net (code "79") (name "Net-(LED3-PadA)") (class "Default")
      (node (ref "LED3") (pin "A") (pinfunction "A_A") (pintype "passive"))
      (node (ref "R3") (pin "2") (pinfunction "2_2") (pintype "passive"))
    )
    (net (code "80") (name "Net-(LED4-PadA)") (class "Default")
      (node (ref "LED4") (pin "A") (pinfunction "A_A") (pintype "passive"))
      (node (ref "R19") (pin "2") (pinfunction "2_2") (pintype "passive"))
    )
    (net (code "81") (name "Net-(R2-Pad1)") (class "Default")
      (node (ref "R2") (pin "1") (pinfunction "1_1") (pintype "passive"))
      (node (ref "U$1") (pin "35") (pinfunction "35_35") (pintype "bidirectional"))
    )
    (net (code "82") (name "Net-(R3-Pad1)") (class "Default")
      (node (ref "R3") (pin "1") (pinfunction "1_1") (pintype "passive"))
      (node (ref "U$1") (pin "36") (pinfunction "36_36") (pintype "bidirectional"))
    )
    (net (code "83") (name "Net-(U$5-+IN)") (class "Default")
      (node (ref "R21") (pin "2") (pinfunction "2_2") (pintype "passive"))
      (node (ref "R22") (pin "1") (pinfunction "1_1") (pintype "passive"))
      (node (ref "U$5") (pin "12") (pinfunction "+IN_12") (pintype "bidirectional"))
    )
    (net (code "84") (name "Net-(U$5--IN)") (class "Default")
      (node (ref "U$5") (pin "10") (pinfunction "COMP_10") (pintype "bidirectional"))
      (node (ref "U$5") (pin "11") (pinfunction "-IN_11") (pintype "bidirectional"))
    )
    (net (code "85") (name "Net-(U$5-VREG1)") (class "Default")
      (node (ref "C30") (pin "1") (pinfunction "1_1") (pintype "passive"))
      (node (ref "U$5") (pin "3") (pinfunction "VREG1_3") (pintype "bidirectional"))
    )
    (net (code "86") (name "Net-(U$5-VREG2)") (class "Default")
      (node (ref "C32") (pin "1") (pinfunction "1_1") (pintype "passive"))
      (node (ref "U$5") (pin "14") (pinfunction "VREG2_14") (pintype "bidirectional"))
    )
    (net (code "87") (name "unconnected-(DC-CONV-Pad1)") (class "Default")
      (node (ref "DC-CONV") (pin "1") (pinfunction "1_1") (pintype "passive"))
    )
    (net (code "88") (name "unconnected-(DC-CONV-Pad3)") (class "Default")
      (node (ref "DC-CONV") (pin "3") (pinfunction "3_3") (pintype "passive"))
    )
    (net (code "89") (name "unconnected-(DC-CONV-Pad4)") (class "Default")
      (node (ref "DC-CONV") (pin "4") (pinfunction "4_4") (pintype "passive"))
    )
    (net (code "90") (name "unconnected-(DC-CONV-Pad5)") (class "Default")
      (node (ref "DC-CONV") (pin "5") (pinfunction "5_5") (pintype "passive"))
    )
    (net (code "91") (name "unconnected-(DC-CONV-Pad6)") (class "Default")
      (node (ref "DC-CONV") (pin "6") (pinfunction "6_6") (pintype "passive"))
    )
    (net (code "92") (name "unconnected-(DC-CONV-Pad7)") (class "Default")
      (node (ref "DC-CONV") (pin "7") (pinfunction "7_7") (pintype "passive"))
    )
    (net (code "93") (name "unconnected-(DC-CONV-Pad8)") (class "Default")
      (node (ref "DC-CONV") (pin "8") (pinfunction "8_8") (pintype "passive"))
    )
    (net (code "94") (name "unconnected-(DC-CONV-Pad9)") (class "Default")
      (node (ref "DC-CONV") (pin "9") (pinfunction "9_9") (pintype "passive"))
    )
    (net (code "95") (name "unconnected-(DC-CONV-Pad10)") (class "Default")
      (node (ref "DC-CONV") (pin "10") (pinfunction "10_10") (pintype "passive"))
    )
    (net (code "96") (name "unconnected-(DC-CONV-Pad11)") (class "Default")
      (node (ref "DC-CONV") (pin "11") (pinfunction "11_11") (pintype "passive"))
    )
    (net (code "97") (name "unconnected-(DC-CONV-Pad12)") (class "Default")
      (node (ref "DC-CONV") (pin "12") (pinfunction "12_12") (pintype "passive"))
    )
    (net (code "98") (name "unconnected-(DC-CONV-Pad13)") (class "Default")
      (node (ref "DC-CONV") (pin "13") (pinfunction "13_13") (pintype "passive"))
    )
    (net (code "99") (name "unconnected-(DC-CONV-Pad15)") (class "Default")
      (node (ref "DC-CONV") (pin "15") (pinfunction "15_15") (pintype "passive"))
    )
    (net (code "100") (name "unconnected-(DC-CONV-Pad17)") (class "Default")
      (node (ref "DC-CONV") (pin "17") (pinfunction "17_17") (pintype "passive"))
    )
    (net (code "101") (name "unconnected-(DC-CONV-Pad18)") (class "Default")
      (node (ref "DC-CONV") (pin "18") (pinfunction "18_18") (pintype "passive"))
    )
    (net (code "102") (name "unconnected-(DC-CONV-Pad19)") (class "Default")
      (node (ref "DC-CONV") (pin "19") (pinfunction "19_19") (pintype "passive"))
    )
    (net (code "103") (name "unconnected-(DC-CONV-Pad20)") (class "Default")
      (node (ref "DC-CONV") (pin "20") (pinfunction "20_20") (pintype "passive"))
    )
    (net (code "104") (name "unconnected-(DC-CONV-Pad21)") (class "Default")
      (node (ref "DC-CONV") (pin "21") (pinfunction "21_21") (pintype "passive"))
    )
    (net (code "105") (name "unconnected-(DC-CONV-Pad22)") (class "Default")
      (node (ref "DC-CONV") (pin "22") (pinfunction "22_22") (pintype "passive"))
    )
    (net (code "106") (name "unconnected-(DC-CONV-Pad24)") (class "Default")
      (node (ref "DC-CONV") (pin "24") (pinfunction "24_24") (pintype "passive"))
    )
    (net (code "107") (name "unconnected-(LR1-DOUT-Pad13)") (class "Default")
      (node (ref "LR1") (pin "13") (pinfunction "DOUT_13") (pintype "output"))
    )
    (net (code "108") (name "unconnected-(LR1-~{EN}-Pad12)") (class "Default")
      (node (ref "LR1") (pin "12") (pinfunction "~{EN}_12") (pintype "input"))
    )
    (net (code "109") (name "unconnected-(LR2-DOUT-Pad13)") (class "Default")
      (node (ref "LR2") (pin "13") (pinfunction "DOUT_13") (pintype "output"))
    )
    (net (code "110") (name "unconnected-(LR2-~{EN}-Pad12)") (class "Default")
      (node (ref "LR2") (pin "12") (pinfunction "~{EN}_12") (pintype "input"))
    )
    (net (code "111") (name "unconnected-(U$1-Pad3)") (class "Default")
      (node (ref "U$1") (pin "3") (pinfunction "3_3") (pintype "bidirectional"))
    )
    (net (code "112") (name "unconnected-(U$1-Pad5V_A)") (class "Default")
      (node (ref "U$1") (pin "5V_A") (pinfunction "5V_A_5V_A") (pintype "bidirectional"))
    )
    (net (code "113") (name "unconnected-(U$1-Pad5V_B)") (class "Default")
      (node (ref "U$1") (pin "5V_B") (pinfunction "5V_B_5V_B") (pintype "bidirectional"))
    )
    (net (code "114") (name "unconnected-(U$1-Pad6)") (class "Default")
      (node (ref "U$1") (pin "6") (pinfunction "6_6") (pintype "bidirectional"))
    )
    (net (code "115") (name "unconnected-(U$1-Pad7)") (class "Default")
      (node (ref "U$1") (pin "7") (pinfunction "7_7") (pintype "bidirectional"))
    )
    (net (code "116") (name "unconnected-(U$1-Pad12)") (class "Default")
      (node (ref "U$1") (pin "12") (pinfunction "12_12") (pintype "bidirectional"))
    )
    (net (code "117") (name "unconnected-(U$1-Pad23)") (class "Default")
      (node (ref "U$1") (pin "23") (pinfunction "23_23") (pintype "bidirectional"))
    )
    (net (code "118") (name "unconnected-(U$1-Pad24)") (class "Default")
      (node (ref "U$1") (pin "24") (pinfunction "24_24") (pintype "bidirectional"))
    )
    (net (code "119") (name "unconnected-(U$1-Pad30)") (class "Default")
      (node (ref "U$1") (pin "30") (pinfunction "30_30") (pintype "bidirectional"))
    )
    (net (code "120") (name "unconnected-(U$1-Pad31)") (class "Default")
      (node (ref "U$1") (pin "31") (pinfunction "31_31") (pintype "bidirectional"))
    )
    (net (code "121") (name "unconnected-(U$1-Pad34)") (class "Default")
      (node (ref "U$1") (pin "34") (pinfunction "34_34") (pintype "bidirectional"))
    )
    (net (code "122") (name "unconnected-(U$1-Pad41)") (class "Default")
      (node (ref "U$1") (pin "41") (pinfunction "41_41") (pintype "bidirectional"))
    )
    (net (code "123") (name "unconnected-(U$1-Pad42)") (class "Default")
      (node (ref "U$1") (pin "42") (pinfunction "42_42") (pintype "bidirectional"))
    )
    (net (code "124") (name "unconnected-(U$1-Pad43)") (class "Default")
      (node (ref "U$1") (pin "43") (pinfunction "43_43") (pintype "bidirectional"))
    )
    (net (code "125") (name "unconnected-(U$1-Pad44)") (class "Default")
      (node (ref "U$1") (pin "44") (pinfunction "44_44") (pintype "bidirectional"))
    )
    (net (code "126") (name "unconnected-(U$1-Pad45)") (class "Default")
      (node (ref "U$1") (pin "45") (pinfunction "45_45") (pintype "bidirectional"))
    )
    (net (code "127") (name "unconnected-(U$1-PadA5)") (class "Default")
      (node (ref "U$1") (pin "A5") (pinfunction "A5_A5") (pintype "bidirectional"))
    )
    (net (code "128") (name "unconnected-(U$1-PadA10)") (class "Default")
      (node (ref "U$1") (pin "A10") (pinfunction "A10_A10") (pintype "bidirectional"))
    )
    (net (code "129") (name "unconnected-(U$1-PadAREF)") (class "Default")
      (node (ref "U$1") (pin "AREF") (pinfunction "AREF_AREF") (pintype "bidirectional"))
    )
    (net (code "130") (name "unconnected-(U$1-PadCANRX)") (class "Default")
      (node (ref "U$1") (pin "CANRX") (pinfunction "CANRX_CANRX") (pintype "bidirectional"))
    )
    (net (code "131") (name "unconnected-(U$1-PadCANTX)") (class "Default")
      (node (ref "U$1") (pin "CANTX") (pinfunction "CANTX_CANTX") (pintype "bidirectional"))
    )
    (net (code "132") (name "unconnected-(U$1-PadDAC0)") (class "Default")
      (node (ref "U$1") (pin "DAC0") (pinfunction "DAC0_DAC0") (pintype "bidirectional"))
    )
    (net (code "133") (name "unconnected-(U$1-PadDAC1)") (class "Default")
      (node (ref "U$1") (pin "DAC1") (pinfunction "DAC1_DAC1") (pintype "bidirectional"))
    )
    (net (code "134") (name "unconnected-(U$1-PadGND1)") (class "Default")
      (node (ref "U$1") (pin "GND1") (pinfunction "GND1_GND1") (pintype "bidirectional"))
    )
    (net (code "135") (name "unconnected-(U$1-PadGND_A)") (class "Default")
      (node (ref "U$1") (pin "GND_A") (pinfunction "GND_A_GND_A") (pintype "bidirectional"))
    )
    (net (code "136") (name "unconnected-(U$1-PadGND_B)") (class "Default")
      (node (ref "U$1") (pin "GND_B") (pinfunction "GND_B_GND_B") (pintype "bidirectional"))
    )
    (net (code "137") (name "unconnected-(U$1-PadGND_DEBUG)") (class "Default")
      (node (ref "U$1") (pin "GND_DEBUG") (pinfunction "GND_DEBUG_GND_DEBUG") (pintype "bidirectional"))
    )
    (net (code "138") (name "unconnected-(U$1-PadGND_ICSP)") (class "Default")
      (node (ref "U$1") (pin "GND_ICSP") (pinfunction "GND_ICSP_GND_ICSP") (pintype "bidirectional"))
    )
    (net (code "139") (name "unconnected-(U$1-PadIOREF)") (class "Default")
      (node (ref "U$1") (pin "IOREF") (pinfunction "IOREF_IOREF") (pintype "bidirectional"))
    )
    (net (code "140") (name "unconnected-(U$1-PadNC)") (class "Default")
      (node (ref "U$1") (pin "NC") (pinfunction "NC_NC") (pintype "bidirectional"))
    )
    (net (code "141") (name "unconnected-(U$1-PadRESET)") (class "Default")
      (node (ref "U$1") (pin "RESET") (pinfunction "RESET_RESET") (pintype "bidirectional"))
    )
    (net (code "142") (name "unconnected-(U$1-PadRESET_DEBUG)") (class "Default")
      (node (ref "U$1") (pin "RESET_DEBUG") (pinfunction "RESET_DEBUG_RESET_DEBUG") (pintype "bidirectional"))
    )
    (net (code "143") (name "unconnected-(U$1-PadRESET_ICSP)") (class "Default")
      (node (ref "U$1") (pin "RESET_ICSP") (pinfunction "RESET_ICSP_RESET_ICSP") (pintype "bidirectional"))
    )
    (net (code "144") (name "unconnected-(U$1-PadRX1)") (class "Default")
      (node (ref "U$1") (pin "RX1") (pinfunction "RX1_RX1") (pintype "bidirectional"))
    )
    (net (code "145") (name "unconnected-(U$1-PadSCL)") (class "Default")
      (node (ref "U$1") (pin "SCL") (pinfunction "SCL_SCL") (pintype "bidirectional"))
    )
    (net (code "146") (name "unconnected-(U$1-PadSCL1)") (class "Default")
      (node (ref "U$1") (pin "SCL1") (pinfunction "SCL1_SCL1") (pintype "bidirectional"))
    )
    (net (code "147") (name "unconnected-(U$1-PadSDA)") (class "Default")
      (node (ref "U$1") (pin "SDA") (pinfunction "SDA_SDA") (pintype "bidirectional"))
    )
    (net (code "148") (name "unconnected-(U$1-PadSDA1)") (class "Default")
      (node (ref "U$1") (pin "SDA1") (pinfunction "SDA1_SDA1") (pintype "bidirectional"))
    )
    (net (code "149") (name "unconnected-(U$1-PadSWCLK_DEBUG)") (class "Default")
      (node (ref "U$1") (pin "SWCLK_DEBUG") (pinfunction "SWCLK_DEBUG_SWCLK_DEBUG") (pintype "bidirectional"))
    )
    (net (code "150") (name "unconnected-(U$1-PadSWDIO_DEBUG)") (class "Default")
      (node (ref "U$1") (pin "SWDIO_DEBUG") (pinfunction "SWDIO_DEBUG_SWDIO_DEBUG") (pintype "bidirectional"))
    )
    (net (code "151") (name "unconnected-(U$1-PadTX1)") (class "Default")
      (node (ref "U$1") (pin "TX1") (pinfunction "TX1_TX1") (pintype "bidirectional"))
    )
    (net (code "152") (name "unconnected-(U$5-EAOUT2-Pad6)") (class "Default")
      (node (ref "U$5") (pin "6") (pinfunction "EAOUT2_6") (pintype "bidirectional"))
    )
    (net (code "153") (name "unconnected-(U$5-NC2-Pad5)") (class "Default")
      (node (ref "U$5") (pin "5") (pinfunction "NC2_5") (pintype "bidirectional"))
    )
    (net (code "154") (name "unconnected-(U$5-REFOUT-Pad13)") (class "Default")
      (node (ref "U$5") (pin "13") (pinfunction "REFOUT_13") (pintype "bidirectional"))
    )
    (net (code "155") (name "unconnected-(U$5-REFOUT1-Pad4)") (class "Default")
      (node (ref "U$5") (pin "4") (pinfunction "REFOUT1_4") (pintype "bidirectional"))
    )
  )
)
